# Battery_Board.net
KiCad netlist of a schematic drawn in EAGLE
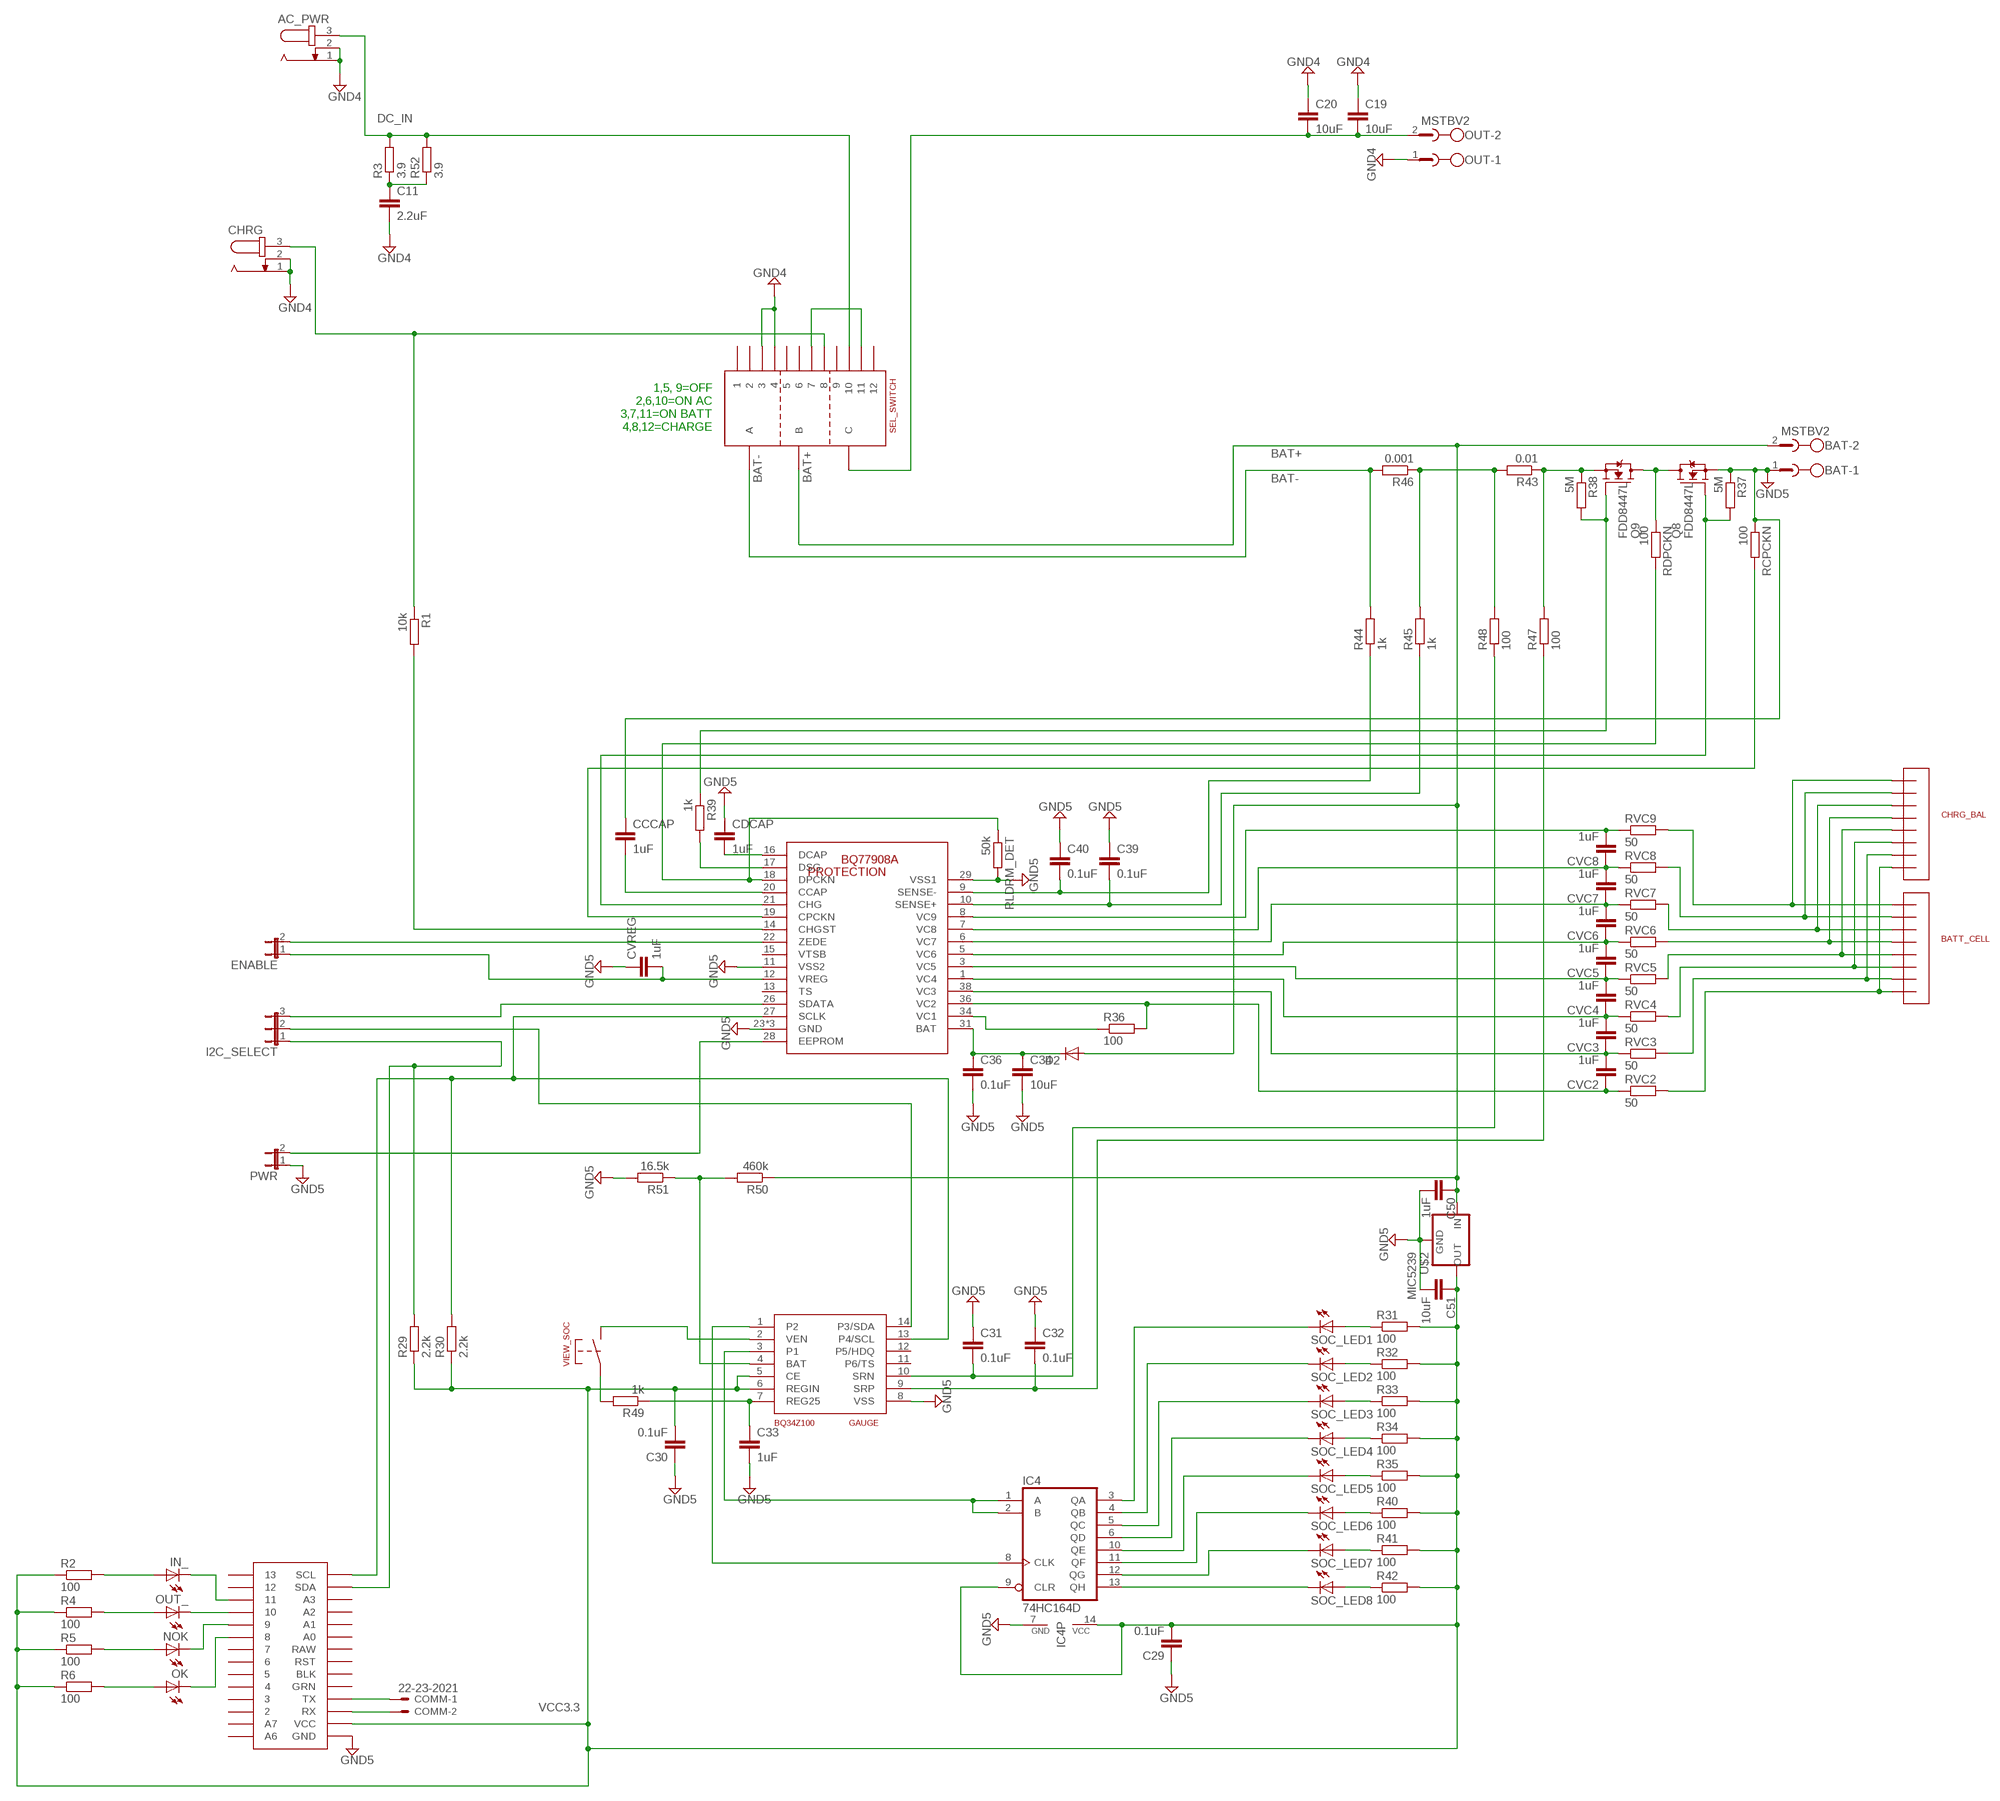
[diagram p0: schematic, sheet 1]

(export (version "E")
  (design (tool "Eeschema 10.0.6"))
  (components
    (comp (ref "AC_PWR")
      (value "JACK-PLUG1")
      (footprint "eagle-import:SPC4078")
      (libsource (lib "eagle-import") (part "JACK-PLUG1"))
    )
    (comp (ref "BAT")
      (value "MSTBV2")
      (footprint "eagle-import:MSTBV2")
      (fields
        (field (name "MPN") "MSTBV 2,5/2-GF-5.08")
        (field (name "MPN_1") "MSTBV 2,5/2-GF-5.08")
        (field (name "OC_FARNELL") "1792792")
        (field (name "OC_NEWARK") "69R9845")
      )
      (libsource (lib "eagle-import") (part "MSTBV2"))
    )
    (comp (ref "BATT_CELL")
      (value "JST-XH-8")
      (footprint "eagle-import:8PIN-2.5MM")
      (libsource (lib "eagle-import") (part "JST-XH-8"))
    )
    (comp (ref "C11")
      (value "2.2uF")
      (footprint "eagle-import:C1206")
      (libsource (lib "eagle-import") (part "C-EUC1206"))
    )
    (comp (ref "C19")
      (value "10uF")
      (footprint "eagle-import:C1812")
      (libsource (lib "eagle-import") (part "C-EUC1812"))
    )
    (comp (ref "C20")
      (value "10uF")
      (footprint "eagle-import:C1812")
      (libsource (lib "eagle-import") (part "C-EUC1812"))
    )
    (comp (ref "C29")
      (value "0.1uF")
      (footprint "eagle-import:C0603")
      (libsource (lib "eagle-import") (part "C-EUC0603"))
    )
    (comp (ref "C30")
      (value "0.1uF")
      (footprint "eagle-import:C0603")
      (libsource (lib "eagle-import") (part "C-EUC0603"))
    )
    (comp (ref "C31")
      (value "0.1uF")
      (footprint "eagle-import:C0603")
      (libsource (lib "eagle-import") (part "C-EUC0603"))
    )
    (comp (ref "C32")
      (value "0.1uF")
      (footprint "eagle-import:C0603")
      (libsource (lib "eagle-import") (part "C-EUC0603"))
    )
    (comp (ref "C33")
      (value "1uF")
      (footprint "eagle-import:C0603")
      (libsource (lib "eagle-import") (part "C-EUC0603"))
    )
    (comp (ref "C34")
      (value "10uF")
      (footprint "eagle-import:C1210")
      (libsource (lib "eagle-import") (part "C-EUC1210"))
    )
    (comp (ref "C36")
      (value "0.1uF")
      (footprint "eagle-import:C1210")
      (libsource (lib "eagle-import") (part "C-EUC1210"))
    )
    (comp (ref "C39")
      (value "0.1uF")
      (footprint "eagle-import:C0603")
      (libsource (lib "eagle-import") (part "C-EUC0603"))
    )
    (comp (ref "C40")
      (value "0.1uF")
      (footprint "eagle-import:C0603")
      (libsource (lib "eagle-import") (part "C-EUC0603"))
    )
    (comp (ref "C50")
      (value "1uF")
      (footprint "eagle-import:C0603")
      (libsource (lib "eagle-import") (part "C-EUC0603"))
    )
    (comp (ref "C51")
      (value "10uF")
      (footprint "eagle-import:C0603")
      (libsource (lib "eagle-import") (part "C-EUC0603"))
    )
    (comp (ref "CCCAP")
      (value "1uF")
      (footprint "eagle-import:C1206")
      (libsource (lib "eagle-import") (part "C-EUC1206"))
    )
    (comp (ref "CDCAP")
      (value "1uF")
      (footprint "eagle-import:C1206")
      (libsource (lib "eagle-import") (part "C-EUC1206"))
    )
    (comp (ref "CHRG")
      (value "JACK-PLUG1")
      (footprint "eagle-import:SPC4078")
      (libsource (lib "eagle-import") (part "JACK-PLUG1"))
    )
    (comp (ref "CHRG_BAL")
      (value "JST-XH-8")
      (footprint "eagle-import:8PIN-2.5MM")
      (libsource (lib "eagle-import") (part "JST-XH-8"))
    )
    (comp (ref "COMM")
      (value "22-23-2021")
      (footprint "eagle-import:22-23-2021")
      (fields (field (name "MF") "MOLEX"))
      (libsource (lib "eagle-import") (part "22-23-2021"))
    )
    (comp (ref "CVC2")
      (value "1uF")
      (footprint "eagle-import:C0603")
      (libsource (lib "eagle-import") (part "C-EUC0603"))
    )
    (comp (ref "CVC3")
      (value "1uF")
      (footprint "eagle-import:C0603")
      (libsource (lib "eagle-import") (part "C-EUC0603"))
    )
    (comp (ref "CVC4")
      (value "1uF")
      (footprint "eagle-import:C0603")
      (libsource (lib "eagle-import") (part "C-EUC0603"))
    )
    (comp (ref "CVC5")
      (value "1uF")
      (footprint "eagle-import:C0603")
      (libsource (lib "eagle-import") (part "C-EUC0603"))
    )
    (comp (ref "CVC6")
      (value "1uF")
      (footprint "eagle-import:C0603")
      (libsource (lib "eagle-import") (part "C-EUC0603"))
    )
    (comp (ref "CVC7")
      (value "1uF")
      (footprint "eagle-import:C0603")
      (libsource (lib "eagle-import") (part "C-EUC0603"))
    )
    (comp (ref "CVC8")
      (value "1uF")
      (footprint "eagle-import:C0603")
      (libsource (lib "eagle-import") (part "C-EUC0603"))
    )
    (comp (ref "CVREG")
      (value "1uF")
      (footprint "eagle-import:C0603")
      (libsource (lib "eagle-import") (part "C-EUC0603"))
    )
    (comp (ref "D2")
      (value "DIODE-SOD123")
      (footprint "eagle-import:SOD123")
      (libsource (lib "eagle-import") (part "DIODE-SOD123"))
    )
    (comp (ref "ENABLE")
      (value "JP1E")
      (footprint "eagle-import:JP1")
      (libsource (lib "eagle-import") (part "JP1E"))
    )
    (comp (ref "GAUGE")
      (value "BQ34Z100")
      (footprint "eagle-import:TSSOP-14-0.65MM")
      (libsource (lib "eagle-import") (part "BQ34Z100"))
    )
    (comp (ref "I2C_SELECT")
      (value "JP2E")
      (footprint "eagle-import:JP2")
      (libsource (lib "eagle-import") (part "JP2E"))
    )
    (comp (ref "IC4")
      (value "74HC164D")
      (footprint "eagle-import:SO14")
      (libsource (lib "eagle-import") (part "74164DHC"))
    )
    (comp (ref "IN_")
      (value "LEDCHIP-LED0603")
      (footprint "eagle-import:CHIP-LED0603")
      (libsource (lib "eagle-import") (part "LEDCHIP-LED0603"))
    )
    (comp (ref "NOK")
      (value "LEDCHIP-LED0603")
      (footprint "eagle-import:CHIP-LED0603")
      (libsource (lib "eagle-import") (part "LEDCHIP-LED0603"))
    )
    (comp (ref "OK")
      (value "LEDCHIP-LED0603")
      (footprint "eagle-import:CHIP-LED0603")
      (libsource (lib "eagle-import") (part "LEDCHIP-LED0603"))
    )
    (comp (ref "OUT")
      (value "MSTBV2")
      (footprint "eagle-import:MSTBV2")
      (fields
        (field (name "MPN") "MSTBV 2,5/2-GF-5.08")
        (field (name "MPN_1") "MSTBV 2,5/2-GF-5.08")
        (field (name "OC_FARNELL") "1792792")
        (field (name "OC_NEWARK") "69R9845")
      )
      (libsource (lib "eagle-import") (part "MSTBV2"))
    )
    (comp (ref "OUT_")
      (value "LEDCHIP-LED0603")
      (footprint "eagle-import:CHIP-LED0603")
      (libsource (lib "eagle-import") (part "LEDCHIP-LED0603"))
    )
    (comp (ref "PROTECTION")
      (value "BQ77908A")
      (footprint "eagle-import:TSSOP-38-0.5MM")
      (libsource (lib "eagle-import") (part "BQ77908A"))
    )
    (comp (ref "PWR")
      (value "JP1E")
      (footprint "eagle-import:JP1")
      (libsource (lib "eagle-import") (part "JP1E"))
    )
    (comp (ref "Q8")
      (value "FDD8447L")
      (footprint "eagle-import:TO252")
      (libsource (lib "eagle-import") (part "FDD8447L"))
    )
    (comp (ref "Q9")
      (value "FDD8447L")
      (footprint "eagle-import:TO252")
      (libsource (lib "eagle-import") (part "FDD8447L"))
    )
    (comp (ref "R1")
      (value "10k")
      (footprint "eagle-import:R0603")
      (libsource (lib "eagle-import") (part "R-EU_R0603"))
    )
    (comp (ref "R2")
      (value "100")
      (footprint "eagle-import:R0603")
      (libsource (lib "eagle-import") (part "R-EU_R0603"))
    )
    (comp (ref "R3")
      (value "3.9")
      (footprint "eagle-import:R1206")
      (libsource (lib "eagle-import") (part "R-EU_R1206"))
    )
    (comp (ref "R4")
      (value "100")
      (footprint "eagle-import:R0603")
      (libsource (lib "eagle-import") (part "R-EU_R0603"))
    )
    (comp (ref "R5")
      (value "100")
      (footprint "eagle-import:R0603")
      (libsource (lib "eagle-import") (part "R-EU_R0603"))
    )
    (comp (ref "R6")
      (value "100")
      (footprint "eagle-import:R0603")
      (libsource (lib "eagle-import") (part "R-EU_R0603"))
    )
    (comp (ref "R29")
      (value "2.2k")
      (footprint "eagle-import:R0603")
      (libsource (lib "eagle-import") (part "R-EU_R0603"))
    )
    (comp (ref "R30")
      (value "2.2k")
      (footprint "eagle-import:R0603")
      (libsource (lib "eagle-import") (part "R-EU_R0603"))
    )
    (comp (ref "R31")
      (value "100")
      (footprint "eagle-import:R0603")
      (libsource (lib "eagle-import") (part "R-EU_R0603"))
    )
    (comp (ref "R32")
      (value "100")
      (footprint "eagle-import:R0603")
      (libsource (lib "eagle-import") (part "R-EU_R0603"))
    )
    (comp (ref "R33")
      (value "100")
      (footprint "eagle-import:R0603")
      (libsource (lib "eagle-import") (part "R-EU_R0603"))
    )
    (comp (ref "R34")
      (value "100")
      (footprint "eagle-import:R0603")
      (libsource (lib "eagle-import") (part "R-EU_R0603"))
    )
    (comp (ref "R35")
      (value "100")
      (footprint "eagle-import:R0603")
      (libsource (lib "eagle-import") (part "R-EU_R0603"))
    )
    (comp (ref "R36")
      (value "100")
      (footprint "eagle-import:R0603")
      (libsource (lib "eagle-import") (part "R-EU_R0603"))
    )
    (comp (ref "R37")
      (value "5M")
      (footprint "eagle-import:R0603")
      (libsource (lib "eagle-import") (part "R-EU_R0603"))
    )
    (comp (ref "R38")
      (value "5M")
      (footprint "eagle-import:R0603")
      (libsource (lib "eagle-import") (part "R-EU_R0603"))
    )
    (comp (ref "R39")
      (value "1k")
      (footprint "eagle-import:R0603")
      (libsource (lib "eagle-import") (part "R-EU_R0603"))
    )
    (comp (ref "R40")
      (value "100")
      (footprint "eagle-import:R0603")
      (libsource (lib "eagle-import") (part "R-EU_R0603"))
    )
    (comp (ref "R41")
      (value "100")
      (footprint "eagle-import:R0603")
      (libsource (lib "eagle-import") (part "R-EU_R0603"))
    )
    (comp (ref "R42")
      (value "100")
      (footprint "eagle-import:R0603")
      (libsource (lib "eagle-import") (part "R-EU_R0603"))
    )
    (comp (ref "R43")
      (value "0.01")
      (footprint "eagle-import:R2010")
      (libsource (lib "eagle-import") (part "R-EU_R2010"))
    )
    (comp (ref "R44")
      (value "1k")
      (footprint "eagle-import:R0603")
      (libsource (lib "eagle-import") (part "R-EU_R0603"))
    )
    (comp (ref "R45")
      (value "1k")
      (footprint "eagle-import:R0603")
      (libsource (lib "eagle-import") (part "R-EU_R0603"))
    )
    (comp (ref "R46")
      (value "0.001")
      (footprint "eagle-import:R2010")
      (libsource (lib "eagle-import") (part "R-EU_R2010"))
    )
    (comp (ref "R47")
      (value "100")
      (footprint "eagle-import:R0603")
      (libsource (lib "eagle-import") (part "R-EU_R0603"))
    )
    (comp (ref "R48")
      (value "100")
      (footprint "eagle-import:R0603")
      (libsource (lib "eagle-import") (part "R-EU_R0603"))
    )
    (comp (ref "R49")
      (value "1k")
      (footprint "eagle-import:R0603")
      (libsource (lib "eagle-import") (part "R-EU_R0603"))
    )
    (comp (ref "R50")
      (value "460k")
      (footprint "eagle-import:R0805")
      (libsource (lib "eagle-import") (part "R-EU_R0805"))
    )
    (comp (ref "R51")
      (value "16.5k")
      (footprint "eagle-import:R0603")
      (libsource (lib "eagle-import") (part "R-EU_R0603"))
    )
    (comp (ref "R52")
      (value "3.9")
      (footprint "eagle-import:R1206")
      (libsource (lib "eagle-import") (part "R-EU_R1206"))
    )
    (comp (ref "RCPCKN")
      (value "100")
      (footprint "eagle-import:R0603")
      (libsource (lib "eagle-import") (part "R-EU_R0603"))
    )
    (comp (ref "RDPCKN")
      (value "100")
      (footprint "eagle-import:R0603")
      (libsource (lib "eagle-import") (part "R-EU_R0603"))
    )
    (comp (ref "RLDRM_DET")
      (value "50k")
      (footprint "eagle-import:R0603")
      (libsource (lib "eagle-import") (part "R-EU_R0603"))
    )
    (comp (ref "RVC2")
      (value "50")
      (footprint "eagle-import:R1206")
      (libsource (lib "eagle-import") (part "R-EU_R1206"))
    )
    (comp (ref "RVC3")
      (value "50")
      (footprint "eagle-import:R1206")
      (libsource (lib "eagle-import") (part "R-EU_R1206"))
    )
    (comp (ref "RVC4")
      (value "50")
      (footprint "eagle-import:R1206")
      (libsource (lib "eagle-import") (part "R-EU_R1206"))
    )
    (comp (ref "RVC5")
      (value "50")
      (footprint "eagle-import:R1206")
      (libsource (lib "eagle-import") (part "R-EU_R1206"))
    )
    (comp (ref "RVC6")
      (value "50")
      (footprint "eagle-import:R1206")
      (libsource (lib "eagle-import") (part "R-EU_R1206"))
    )
    (comp (ref "RVC7")
      (value "50")
      (footprint "eagle-import:R1206")
      (libsource (lib "eagle-import") (part "R-EU_R1206"))
    )
    (comp (ref "RVC8")
      (value "50")
      (footprint "eagle-import:R1206")
      (libsource (lib "eagle-import") (part "R-EU_R1206"))
    )
    (comp (ref "RVC9")
      (value "50")
      (footprint "eagle-import:R1206")
      (libsource (lib "eagle-import") (part "R-EU_R1206"))
    )
    (comp (ref "SEL_SWITCH")
      (value "CK1026")
      (footprint "eagle-import:CK1026")
      (libsource (lib "eagle-import") (part "CK1026"))
    )
    (comp (ref "SOC_LED1")
      (value "LEDCHIP-LED0603")
      (footprint "eagle-import:CHIP-LED0603")
      (libsource (lib "eagle-import") (part "LEDCHIP-LED0603"))
    )
    (comp (ref "SOC_LED2")
      (value "LEDCHIP-LED0603")
      (footprint "eagle-import:CHIP-LED0603")
      (libsource (lib "eagle-import") (part "LEDCHIP-LED0603"))
    )
    (comp (ref "SOC_LED3")
      (value "LEDCHIP-LED0603")
      (footprint "eagle-import:CHIP-LED0603")
      (libsource (lib "eagle-import") (part "LEDCHIP-LED0603"))
    )
    (comp (ref "SOC_LED4")
      (value "LEDCHIP-LED0603")
      (footprint "eagle-import:CHIP-LED0603")
      (libsource (lib "eagle-import") (part "LEDCHIP-LED0603"))
    )
    (comp (ref "SOC_LED5")
      (value "LEDCHIP-LED0603")
      (footprint "eagle-import:CHIP-LED0603")
      (libsource (lib "eagle-import") (part "LEDCHIP-LED0603"))
    )
    (comp (ref "SOC_LED6")
      (value "LEDCHIP-LED0603")
      (footprint "eagle-import:CHIP-LED0603")
      (libsource (lib "eagle-import") (part "LEDCHIP-LED0603"))
    )
    (comp (ref "SOC_LED7")
      (value "LEDCHIP-LED0603")
      (footprint "eagle-import:CHIP-LED0603")
      (libsource (lib "eagle-import") (part "LEDCHIP-LED0603"))
    )
    (comp (ref "SOC_LED8")
      (value "LEDCHIP-LED0603")
      (footprint "eagle-import:CHIP-LED0603")
      (libsource (lib "eagle-import") (part "LEDCHIP-LED0603"))
    )
    (comp (ref "U$1")
      (value "ARDUINO-MINI-PRO")
      (footprint "eagle-import:ARDUINO-MINI-PRO")
      (libsource (lib "eagle-import") (part "ARDUINO-MINI-PRO"))
    )
    (comp (ref "U$2")
      (value "MIC5239")
      (footprint "eagle-import:SOT223")
      (libsource (lib "eagle-import") (part "MIC5239"))
    )
    (comp (ref "VIEW_SOC")
      (value "PUSHBUTTON")
      (footprint "eagle-import:PUSHBUTTON")
      (libsource (lib "eagle-import") (part "PUSHBUTTON"))
    )
  )
  (nets
    (net (code "1") (name "/BAT+") (class "Default")
      (node (ref "BAT") (pin "2") (pinfunction "1_2") (pintype "passive"))
      (node (ref "C50") (pin "1") (pinfunction "1_1") (pintype "passive"))
      (node (ref "D2") (pin "A") (pinfunction "A_A") (pintype "passive"))
      (node (ref "R50") (pin "1") (pinfunction "1_1") (pintype "passive"))
      (node (ref "SEL_SWITCH") (pin "B") (pinfunction "B_B") (pintype "bidirectional"))
      (node (ref "U$2") (pin "1") (pinfunction "IN_1") (pintype "input"))
    )
    (net (code "2") (name "/BAT-") (class "Default")
      (node (ref "R44") (pin "2") (pinfunction "2_2") (pintype "passive"))
      (node (ref "R46") (pin "2") (pinfunction "2_2") (pintype "passive"))
      (node (ref "SEL_SWITCH") (pin "A") (pinfunction "A_A") (pintype "bidirectional"))
    )
    (net (code "3") (name "/DC_IN") (class "Default")
      (node (ref "AC_PWR") (pin "3") (pinfunction "3_3") (pintype "passive"))
      (node (ref "R3") (pin "2") (pinfunction "2_2") (pintype "passive"))
      (node (ref "R52") (pin "2") (pinfunction "2_2") (pintype "passive"))
      (node (ref "SEL_SWITCH") (pin "10") (pinfunction "10_10") (pintype "bidirectional"))
    )
    (net (code "4") (name "/VCC3.3") (class "Default")
      (node (ref "C29") (pin "2") (pinfunction "2_2") (pintype "passive"))
      (node (ref "C30") (pin "2") (pinfunction "2_2") (pintype "passive"))
      (node (ref "C51") (pin "1") (pinfunction "1_1") (pintype "passive"))
      (node (ref "GAUGE") (pin "5") (pinfunction "CE_5") (pintype "bidirectional"))
      (node (ref "GAUGE") (pin "6") (pinfunction "REGIN_6") (pintype "bidirectional"))
      (node (ref "IC4") (pin "14") (pinfunction "VCC_14") (pintype "power_in"))
      (node (ref "IC4") (pin "9") (pinfunction "CLR_9") (pintype "input"))
      (node (ref "R2") (pin "1") (pinfunction "1_1") (pintype "passive"))
      (node (ref "R29") (pin "1") (pinfunction "1_1") (pintype "passive"))
      (node (ref "R30") (pin "1") (pinfunction "1_1") (pintype "passive"))
      (node (ref "R31") (pin "2") (pinfunction "2_2") (pintype "passive"))
      (node (ref "R32") (pin "2") (pinfunction "2_2") (pintype "passive"))
      (node (ref "R33") (pin "2") (pinfunction "2_2") (pintype "passive"))
      (node (ref "R34") (pin "2") (pinfunction "2_2") (pintype "passive"))
      (node (ref "R35") (pin "2") (pinfunction "2_2") (pintype "passive"))
      (node (ref "R4") (pin "1") (pinfunction "1_1") (pintype "passive"))
      (node (ref "R40") (pin "2") (pinfunction "2_2") (pintype "passive"))
      (node (ref "R41") (pin "2") (pinfunction "2_2") (pintype "passive"))
      (node (ref "R42") (pin "2") (pinfunction "2_2") (pintype "passive"))
      (node (ref "R5") (pin "1") (pinfunction "1_1") (pintype "passive"))
      (node (ref "R6") (pin "1") (pinfunction "1_1") (pintype "passive"))
      (node (ref "U$1") (pin "VCC") (pinfunction "VCC_VCC") (pintype "bidirectional"))
      (node (ref "U$2") (pin "3") (pinfunction "OUT_3") (pintype "passive"))
    )
    (net (code "5") (name "GND4") (class "Default")
      (node (ref "AC_PWR") (pin "1") (pinfunction "1_1") (pintype "passive"))
      (node (ref "AC_PWR") (pin "2") (pinfunction "2_2") (pintype "passive"))
      (node (ref "C11") (pin "2") (pinfunction "2_2") (pintype "passive"))
      (node (ref "C19") (pin "1") (pinfunction "1_1") (pintype "passive"))
      (node (ref "C20") (pin "1") (pinfunction "1_1") (pintype "passive"))
      (node (ref "CHRG") (pin "1") (pinfunction "1_1") (pintype "passive"))
      (node (ref "CHRG") (pin "2") (pinfunction "2_2") (pintype "passive"))
      (node (ref "OUT") (pin "1") (pinfunction "1_1") (pintype "passive"))
      (node (ref "SEL_SWITCH") (pin "3") (pinfunction "3_3") (pintype "bidirectional"))
      (node (ref "SEL_SWITCH") (pin "4") (pinfunction "4_4") (pintype "bidirectional"))
    )
    (net (code "6") (name "GND5") (class "Default")
      (node (ref "BAT") (pin "1") (pinfunction "1_1") (pintype "passive"))
      (node (ref "C29") (pin "1") (pinfunction "1_1") (pintype "passive"))
      (node (ref "C30") (pin "1") (pinfunction "1_1") (pintype "passive"))
      (node (ref "C31") (pin "1") (pinfunction "1_1") (pintype "passive"))
      (node (ref "C32") (pin "1") (pinfunction "1_1") (pintype "passive"))
      (node (ref "C33") (pin "2") (pinfunction "2_2") (pintype "passive"))
      (node (ref "C34") (pin "2") (pinfunction "2_2") (pintype "passive"))
      (node (ref "C36") (pin "2") (pinfunction "2_2") (pintype "passive"))
      (node (ref "C39") (pin "1") (pinfunction "1_1") (pintype "passive"))
      (node (ref "C40") (pin "1") (pinfunction "1_1") (pintype "passive"))
      (node (ref "C50") (pin "2") (pinfunction "2_2") (pintype "passive"))
      (node (ref "C51") (pin "2") (pinfunction "2_2") (pintype "passive"))
      (node (ref "CCCAP") (pin "1") (pinfunction "1_1") (pintype "passive"))
      (node (ref "CDCAP") (pin "1") (pinfunction "1_1") (pintype "passive"))
      (node (ref "CVREG") (pin "1") (pinfunction "1_1") (pintype "passive"))
      (node (ref "GAUGE") (pin "8") (pinfunction "VSS_8") (pintype "bidirectional"))
      (node (ref "IC4") (pin "7") (pinfunction "GND_7") (pintype "power_in"))
      (node (ref "PROTECTION") (pin "11") (pinfunction "VSS2_11") (pintype "bidirectional"))
      (node (ref "PROTECTION") (pin "23") (pinfunction "GND_23") (pintype "bidirectional"))
      (node (ref "PROTECTION") (pin "24") (pinfunction "GND_24") (pintype "bidirectional"))
      (node (ref "PROTECTION") (pin "25") (pinfunction "GND_25") (pintype "bidirectional"))
      (node (ref "PROTECTION") (pin "29") (pinfunction "VSS1_29") (pintype "bidirectional"))
      (node (ref "PWR") (pin "1") (pinfunction "1_1") (pintype "passive"))
      (node (ref "Q8") (pin "2") (pinfunction "S_2") (pintype "passive"))
      (node (ref "R37") (pin "1") (pinfunction "1_1") (pintype "passive"))
      (node (ref "R51") (pin "2") (pinfunction "2_2") (pintype "passive"))
      (node (ref "RCPCKN") (pin "1") (pinfunction "1_1") (pintype "passive"))
      (node (ref "RLDRM_DET") (pin "2") (pinfunction "2_2") (pintype "passive"))
      (node (ref "U$1") (pin "GND") (pinfunction "GND_GND") (pintype "bidirectional"))
      (node (ref "U$2") (pin "2") (pinfunction "GND_2") (pintype "input"))
      (node (ref "U$2") (pin "4") (pinfunction "GND_4") (pintype "input"))
    )
    (net (code "7") (name "Net-(BATT_CELL-PadP$1)") (class "Default")
      (node (ref "BATT_CELL") (pin "P$1") (pinfunction "P$1_P$1") (pintype "bidirectional"))
      (node (ref "CHRG_BAL") (pin "P$1") (pinfunction "P$1_P$1") (pintype "bidirectional"))
      (node (ref "RVC9") (pin "2") (pinfunction "2_2") (pintype "passive"))
    )
    (net (code "8") (name "Net-(BATT_CELL-PadP$2)") (class "Default")
      (node (ref "BATT_CELL") (pin "P$2") (pinfunction "P$2_P$2") (pintype "bidirectional"))
      (node (ref "CHRG_BAL") (pin "P$2") (pinfunction "P$2_P$2") (pintype "bidirectional"))
      (node (ref "RVC8") (pin "2") (pinfunction "2_2") (pintype "passive"))
    )
    (net (code "9") (name "Net-(BATT_CELL-PadP$3)") (class "Default")
      (node (ref "BATT_CELL") (pin "P$3") (pinfunction "P$3_P$3") (pintype "bidirectional"))
      (node (ref "CHRG_BAL") (pin "P$3") (pinfunction "P$3_P$3") (pintype "bidirectional"))
      (node (ref "RVC7") (pin "2") (pinfunction "2_2") (pintype "passive"))
    )
    (net (code "10") (name "Net-(BATT_CELL-PadP$4)") (class "Default")
      (node (ref "BATT_CELL") (pin "P$4") (pinfunction "P$4_P$4") (pintype "bidirectional"))
      (node (ref "CHRG_BAL") (pin "P$4") (pinfunction "P$4_P$4") (pintype "bidirectional"))
      (node (ref "RVC6") (pin "2") (pinfunction "2_2") (pintype "passive"))
    )
    (net (code "11") (name "Net-(BATT_CELL-PadP$5)") (class "Default")
      (node (ref "BATT_CELL") (pin "P$5") (pinfunction "P$5_P$5") (pintype "bidirectional"))
      (node (ref "CHRG_BAL") (pin "P$5") (pinfunction "P$5_P$5") (pintype "bidirectional"))
      (node (ref "RVC5") (pin "2") (pinfunction "2_2") (pintype "passive"))
    )
    (net (code "12") (name "Net-(BATT_CELL-PadP$6)") (class "Default")
      (node (ref "BATT_CELL") (pin "P$6") (pinfunction "P$6_P$6") (pintype "bidirectional"))
      (node (ref "CHRG_BAL") (pin "P$6") (pinfunction "P$6_P$6") (pintype "bidirectional"))
      (node (ref "RVC4") (pin "2") (pinfunction "2_2") (pintype "passive"))
    )
    (net (code "13") (name "Net-(BATT_CELL-PadP$7)") (class "Default")
      (node (ref "BATT_CELL") (pin "P$7") (pinfunction "P$7_P$7") (pintype "bidirectional"))
      (node (ref "CHRG_BAL") (pin "P$7") (pinfunction "P$7_P$7") (pintype "bidirectional"))
      (node (ref "RVC3") (pin "2") (pinfunction "2_2") (pintype "passive"))
    )
    (net (code "14") (name "Net-(BATT_CELL-PadP$8)") (class "Default")
      (node (ref "BATT_CELL") (pin "P$8") (pinfunction "P$8_P$8") (pintype "bidirectional"))
      (node (ref "CHRG_BAL") (pin "P$8") (pinfunction "P$8_P$8") (pintype "bidirectional"))
      (node (ref "RVC2") (pin "2") (pinfunction "2_2") (pintype "passive"))
    )
    (net (code "15") (name "Net-(C11-Pad1)") (class "Default")
      (node (ref "C11") (pin "1") (pinfunction "1_1") (pintype "passive"))
      (node (ref "R3") (pin "1") (pinfunction "1_1") (pintype "passive"))
      (node (ref "R52") (pin "1") (pinfunction "1_1") (pintype "passive"))
    )
    (net (code "16") (name "Net-(CHRG-Pad3)") (class "Default")
      (node (ref "CHRG") (pin "3") (pinfunction "3_3") (pintype "passive"))
      (node (ref "R1") (pin "1") (pinfunction "1_1") (pintype "passive"))
      (node (ref "SEL_SWITCH") (pin "8") (pinfunction "8_8") (pintype "bidirectional"))
    )
    (net (code "17") (name "Net-(COMMA-S)") (class "Default")
      (node (ref "COMM") (pin "1") (pinfunction "S_1") (pintype "passive"))
      (node (ref "U$1") (pin "TXO") (pinfunction "TX_TXO") (pintype "bidirectional"))
    )
    (net (code "18") (name "Net-(COMMB-S)") (class "Default")
      (node (ref "COMM") (pin "2") (pinfunction "S_2") (pintype "passive"))
      (node (ref "U$1") (pin "RXI") (pinfunction "RX_RXI") (pintype "bidirectional"))
    )
    (net (code "19") (name "Net-(GAUGE-BAT)") (class "Default")
      (node (ref "GAUGE") (pin "4") (pinfunction "BAT_4") (pintype "bidirectional"))
      (node (ref "R50") (pin "2") (pinfunction "2_2") (pintype "passive"))
      (node (ref "R51") (pin "1") (pinfunction "1_1") (pintype "passive"))
    )
    (net (code "20") (name "Net-(GAUGE-P1)") (class "Default")
      (node (ref "GAUGE") (pin "3") (pinfunction "P1_3") (pintype "bidirectional"))
      (node (ref "IC4") (pin "1") (pinfunction "A_1") (pintype "input"))
      (node (ref "IC4") (pin "2") (pinfunction "B_2") (pintype "input"))
    )
    (net (code "21") (name "Net-(GAUGE-P2)") (class "Default")
      (node (ref "GAUGE") (pin "1") (pinfunction "P2_1") (pintype "bidirectional"))
      (node (ref "IC4") (pin "8") (pinfunction "CLK_8") (pintype "input"))
    )
    (net (code "22") (name "Net-(GAUGE-P3{slash}SDA)") (class "Default")
      (node (ref "GAUGE") (pin "14") (pinfunction "P3/SDA_14") (pintype "bidirectional"))
      (node (ref "I2C_SELECT") (pin "2") (pinfunction "2_2") (pintype "passive"))
    )
    (net (code "23") (name "Net-(GAUGE-P4{slash}SCL)") (class "Default")
      (node (ref "GAUGE") (pin "13") (pinfunction "P4/SCL_13") (pintype "bidirectional"))
      (node (ref "PROTECTION") (pin "27") (pinfunction "SCLK_27") (pintype "bidirectional"))
      (node (ref "R30") (pin "2") (pinfunction "2_2") (pintype "passive"))
      (node (ref "U$1") (pin "A5") (pinfunction "SCL_A5") (pintype "bidirectional"))
    )
    (net (code "24") (name "Net-(GAUGE-REG25)") (class "Default")
      (node (ref "C33") (pin "1") (pinfunction "1_1") (pintype "passive"))
      (node (ref "GAUGE") (pin "7") (pinfunction "REG25_7") (pintype "bidirectional"))
      (node (ref "R49") (pin "1") (pinfunction "1_1") (pintype "passive"))
    )
    (net (code "25") (name "Net-(GAUGE-SRN)") (class "Default")
      (node (ref "C31") (pin "2") (pinfunction "2_2") (pintype "passive"))
      (node (ref "GAUGE") (pin "10") (pinfunction "SRN_10") (pintype "bidirectional"))
      (node (ref "R48") (pin "1") (pinfunction "1_1") (pintype "passive"))
    )
    (net (code "26") (name "Net-(GAUGE-SRP)") (class "Default")
      (node (ref "C32") (pin "2") (pinfunction "2_2") (pintype "passive"))
      (node (ref "GAUGE") (pin "9") (pinfunction "SRP_9") (pintype "bidirectional"))
      (node (ref "R47") (pin "1") (pinfunction "1_1") (pintype "passive"))
    )
    (net (code "27") (name "Net-(GAUGE-VEN)") (class "Default")
      (node (ref "GAUGE") (pin "2") (pinfunction "VEN_2") (pintype "bidirectional"))
      (node (ref "VIEW_SOC") (pin "P$3") (pinfunction "P$2_P$3") (pintype "bidirectional"))
      (node (ref "VIEW_SOC") (pin "P$4") (pinfunction "P$2_P$4") (pintype "bidirectional"))
    )
    (net (code "28") (name "Net-(IC4A-QA)") (class "Default")
      (node (ref "IC4") (pin "3") (pinfunction "QA_3") (pintype "output"))
      (node (ref "SOC_LED1") (pin "C") (pinfunction "C_C") (pintype "passive"))
    )
    (net (code "29") (name "Net-(IC4A-QB)") (class "Default")
      (node (ref "IC4") (pin "4") (pinfunction "QB_4") (pintype "output"))
      (node (ref "SOC_LED2") (pin "C") (pinfunction "C_C") (pintype "passive"))
    )
    (net (code "30") (name "Net-(IC4A-QC)") (class "Default")
      (node (ref "IC4") (pin "5") (pinfunction "QC_5") (pintype "output"))
      (node (ref "SOC_LED3") (pin "C") (pinfunction "C_C") (pintype "passive"))
    )
    (net (code "31") (name "Net-(IC4A-QD)") (class "Default")
      (node (ref "IC4") (pin "6") (pinfunction "QD_6") (pintype "output"))
      (node (ref "SOC_LED4") (pin "C") (pinfunction "C_C") (pintype "passive"))
    )
    (net (code "32") (name "Net-(IC4A-QE)") (class "Default")
      (node (ref "IC4") (pin "10") (pinfunction "QE_10") (pintype "output"))
      (node (ref "SOC_LED5") (pin "C") (pinfunction "C_C") (pintype "passive"))
    )
    (net (code "33") (name "Net-(IC4A-QF)") (class "Default")
      (node (ref "IC4") (pin "11") (pinfunction "QF_11") (pintype "output"))
      (node (ref "SOC_LED6") (pin "C") (pinfunction "C_C") (pintype "passive"))
    )
    (net (code "34") (name "Net-(IC4A-QG)") (class "Default")
      (node (ref "IC4") (pin "12") (pinfunction "QG_12") (pintype "output"))
      (node (ref "SOC_LED7") (pin "C") (pinfunction "C_C") (pintype "passive"))
    )
    (net (code "35") (name "Net-(IC4A-QH)") (class "Default")
      (node (ref "IC4") (pin "13") (pinfunction "QH_13") (pintype "output"))
      (node (ref "SOC_LED8") (pin "C") (pinfunction "C_C") (pintype "passive"))
    )
    (net (code "36") (name "Net-(IN_-PadA)") (class "Default")
      (node (ref "IN_") (pin "A") (pinfunction "A_A") (pintype "passive"))
      (node (ref "R2") (pin "2") (pinfunction "2_2") (pintype "passive"))
    )
    (net (code "37") (name "Net-(IN_-PadC)") (class "Default")
      (node (ref "IN_") (pin "C") (pinfunction "C_C") (pintype "passive"))
      (node (ref "U$1") (pin "11") (pinfunction "11_11") (pintype "bidirectional"))
    )
    (net (code "38") (name "Net-(NOK-PadA)") (class "Default")
      (node (ref "NOK") (pin "A") (pinfunction "A_A") (pintype "passive"))
      (node (ref "R5") (pin "2") (pinfunction "2_2") (pintype "passive"))
    )
    (net (code "39") (name "Net-(NOK-PadC)") (class "Default")
      (node (ref "NOK") (pin "C") (pinfunction "C_C") (pintype "passive"))
      (node (ref "U$1") (pin "9") (pinfunction "9_9") (pintype "bidirectional"))
    )
    (net (code "40") (name "Net-(OK-PadA)") (class "Default")
      (node (ref "OK") (pin "A") (pinfunction "A_A") (pintype "passive"))
      (node (ref "R6") (pin "2") (pinfunction "2_2") (pintype "passive"))
    )
    (net (code "41") (name "Net-(OK-PadC)") (class "Default")
      (node (ref "OK") (pin "C") (pinfunction "C_C") (pintype "passive"))
      (node (ref "U$1") (pin "8") (pinfunction "8_8") (pintype "bidirectional"))
    )
    (net (code "42") (name "Net-(OUTB-1)") (class "Default")
      (node (ref "C19") (pin "2") (pinfunction "2_2") (pintype "passive"))
      (node (ref "C20") (pin "2") (pinfunction "2_2") (pintype "passive"))
      (node (ref "OUT") (pin "2") (pinfunction "1_2") (pintype "passive"))
      (node (ref "SEL_SWITCH") (pin "C") (pinfunction "C_C") (pintype "bidirectional"))
    )
    (net (code "43") (name "Net-(OUT_-PadA)") (class "Default")
      (node (ref "OUT_") (pin "A") (pinfunction "A_A") (pintype "passive"))
      (node (ref "R4") (pin "2") (pinfunction "2_2") (pintype "passive"))
    )
    (net (code "44") (name "Net-(OUT_-PadC)") (class "Default")
      (node (ref "OUT_") (pin "C") (pinfunction "C_C") (pintype "passive"))
      (node (ref "U$1") (pin "10") (pinfunction "10_10") (pintype "bidirectional"))
    )
    (net (code "45") (name "Net-(PROTECTION-BAT)") (class "Default")
      (node (ref "C34") (pin "1") (pinfunction "1_1") (pintype "passive"))
      (node (ref "C36") (pin "1") (pinfunction "1_1") (pintype "passive"))
      (node (ref "D2") (pin "C") (pinfunction "C_C") (pintype "passive"))
      (node (ref "PROTECTION") (pin "31") (pinfunction "BAT_31") (pintype "bidirectional"))
    )
    (net (code "46") (name "Net-(PROTECTION-CCAP)") (class "Default")
      (node (ref "CCCAP") (pin "2") (pinfunction "2_2") (pintype "passive"))
      (node (ref "PROTECTION") (pin "20") (pinfunction "CCAP_20") (pintype "bidirectional"))
    )
    (net (code "47") (name "Net-(PROTECTION-CHG)") (class "Default")
      (node (ref "PROTECTION") (pin "21") (pinfunction "CHG_21") (pintype "bidirectional"))
      (node (ref "Q8") (pin "1") (pinfunction "G_1") (pintype "passive"))
      (node (ref "R37") (pin "2") (pinfunction "2_2") (pintype "passive"))
    )
    (net (code "48") (name "Net-(PROTECTION-CHGST)") (class "Default")
      (node (ref "PROTECTION") (pin "14") (pinfunction "CHGST_14") (pintype "bidirectional"))
      (node (ref "R1") (pin "2") (pinfunction "2_2") (pintype "passive"))
    )
    (net (code "49") (name "Net-(PROTECTION-CPCKN)") (class "Default")
      (node (ref "PROTECTION") (pin "19") (pinfunction "CPCKN_19") (pintype "bidirectional"))
      (node (ref "RCPCKN") (pin "2") (pinfunction "2_2") (pintype "passive"))
    )
    (net (code "50") (name "Net-(PROTECTION-DCAP)") (class "Default")
      (node (ref "CDCAP") (pin "2") (pinfunction "2_2") (pintype "passive"))
      (node (ref "PROTECTION") (pin "16") (pinfunction "DCAP_16") (pintype "bidirectional"))
    )
    (net (code "51") (name "Net-(PROTECTION-DPCKN)") (class "Default")
      (node (ref "PROTECTION") (pin "18") (pinfunction "DPCKN_18") (pintype "bidirectional"))
      (node (ref "RDPCKN") (pin "2") (pinfunction "2_2") (pintype "passive"))
      (node (ref "RLDRM_DET") (pin "1") (pinfunction "1_1") (pintype "passive"))
    )
    (net (code "52") (name "Net-(PROTECTION-DSG)") (class "Default")
      (node (ref "PROTECTION") (pin "17") (pinfunction "DSG_17") (pintype "bidirectional"))
      (node (ref "R39") (pin "2") (pinfunction "2_2") (pintype "passive"))
    )
    (net (code "53") (name "Net-(PROTECTION-EEPROM)") (class "Default")
      (node (ref "PROTECTION") (pin "28") (pinfunction "EEPROM_28") (pintype "bidirectional"))
      (node (ref "PWR") (pin "2") (pinfunction "2_2") (pintype "passive"))
    )
    (net (code "54") (name "Net-(PROTECTION-SDATA)") (class "Default")
      (node (ref "I2C_SELECT") (pin "3") (pinfunction "3_3") (pintype "passive"))
      (node (ref "PROTECTION") (pin "26") (pinfunction "SDATA_26") (pintype "bidirectional"))
    )
    (net (code "55") (name "Net-(PROTECTION-SENSE+)") (class "Default")
      (node (ref "C39") (pin "2") (pinfunction "2_2") (pintype "passive"))
      (node (ref "PROTECTION") (pin "10") (pinfunction "SENSE+_10") (pintype "bidirectional"))
      (node (ref "R45") (pin "1") (pinfunction "1_1") (pintype "passive"))
    )
    (net (code "56") (name "Net-(PROTECTION-SENSE-)") (class "Default")
      (node (ref "C40") (pin "2") (pinfunction "2_2") (pintype "passive"))
      (node (ref "PROTECTION") (pin "9") (pinfunction "SENSE-_9") (pintype "bidirectional"))
      (node (ref "R44") (pin "1") (pinfunction "1_1") (pintype "passive"))
    )
    (net (code "57") (name "Net-(PROTECTION-VC1)") (class "Default")
      (node (ref "PROTECTION") (pin "34") (pinfunction "VC1_34") (pintype "bidirectional"))
      (node (ref "R36") (pin "1") (pinfunction "1_1") (pintype "passive"))
    )
    (net (code "58") (name "Net-(PROTECTION-VC2)") (class "Default")
      (node (ref "CVC2") (pin "1") (pinfunction "1_1") (pintype "passive"))
      (node (ref "PROTECTION") (pin "36") (pinfunction "VC2_36") (pintype "bidirectional"))
      (node (ref "R36") (pin "2") (pinfunction "2_2") (pintype "passive"))
      (node (ref "RVC2") (pin "1") (pinfunction "1_1") (pintype "passive"))
    )
    (net (code "59") (name "Net-(PROTECTION-VC3)") (class "Default")
      (node (ref "CVC2") (pin "2") (pinfunction "2_2") (pintype "passive"))
      (node (ref "CVC3") (pin "1") (pinfunction "1_1") (pintype "passive"))
      (node (ref "PROTECTION") (pin "38") (pinfunction "VC3_38") (pintype "bidirectional"))
      (node (ref "RVC3") (pin "1") (pinfunction "1_1") (pintype "passive"))
    )
    (net (code "60") (name "Net-(PROTECTION-VC4)") (class "Default")
      (node (ref "CVC3") (pin "2") (pinfunction "2_2") (pintype "passive"))
      (node (ref "CVC4") (pin "1") (pinfunction "1_1") (pintype "passive"))
      (node (ref "PROTECTION") (pin "1") (pinfunction "VC4_1") (pintype "bidirectional"))
      (node (ref "RVC4") (pin "1") (pinfunction "1_1") (pintype "passive"))
    )
    (net (code "61") (name "Net-(PROTECTION-VC5)") (class "Default")
      (node (ref "CVC4") (pin "2") (pinfunction "2_2") (pintype "passive"))
      (node (ref "CVC5") (pin "1") (pinfunction "1_1") (pintype "passive"))
      (node (ref "PROTECTION") (pin "3") (pinfunction "VC5_3") (pintype "bidirectional"))
      (node (ref "RVC5") (pin "1") (pinfunction "1_1") (pintype "passive"))
    )
    (net (code "62") (name "Net-(PROTECTION-VC6)") (class "Default")
      (node (ref "CVC5") (pin "2") (pinfunction "2_2") (pintype "passive"))
      (node (ref "CVC6") (pin "1") (pinfunction "1_1") (pintype "passive"))
      (node (ref "PROTECTION") (pin "5") (pinfunction "VC6_5") (pintype "bidirectional"))
      (node (ref "RVC6") (pin "1") (pinfunction "1_1") (pintype "passive"))
    )
    (net (code "63") (name "Net-(PROTECTION-VC7)") (class "Default")
      (node (ref "CVC6") (pin "2") (pinfunction "2_2") (pintype "passive"))
      (node (ref "CVC7") (pin "1") (pinfunction "1_1") (pintype "passive"))
      (node (ref "PROTECTION") (pin "6") (pinfunction "VC7_6") (pintype "bidirectional"))
      (node (ref "RVC7") (pin "1") (pinfunction "1_1") (pintype "passive"))
    )
    (net (code "64") (name "Net-(PROTECTION-VC8)") (class "Default")
      (node (ref "CVC7") (pin "2") (pinfunction "2_2") (pintype "passive"))
      (node (ref "CVC8") (pin "1") (pinfunction "1_1") (pintype "passive"))
      (node (ref "PROTECTION") (pin "7") (pinfunction "VC8_7") (pintype "bidirectional"))
      (node (ref "RVC8") (pin "1") (pinfunction "1_1") (pintype "passive"))
    )
    (net (code "65") (name "Net-(PROTECTION-VC9)") (class "Default")
      (node (ref "CVC8") (pin "2") (pinfunction "2_2") (pintype "passive"))
      (node (ref "PROTECTION") (pin "8") (pinfunction "VC9_8") (pintype "bidirectional"))
      (node (ref "RVC9") (pin "1") (pinfunction "1_1") (pintype "passive"))
    )
    (net (code "66") (name "Net-(PROTECTION-VREG)") (class "Default")
      (node (ref "CVREG") (pin "2") (pinfunction "2_2") (pintype "passive"))
      (node (ref "ENABLE") (pin "1") (pinfunction "1_1") (pintype "passive"))
      (node (ref "PROTECTION") (pin "12") (pinfunction "VREG_12") (pintype "bidirectional"))
    )
    (net (code "67") (name "Net-(PROTECTION-ZEDE)") (class "Default")
      (node (ref "ENABLE") (pin "2") (pinfunction "2_2") (pintype "passive"))
      (node (ref "PROTECTION") (pin "22") (pinfunction "ZEDE_22") (pintype "bidirectional"))
    )
    (net (code "68") (name "Net-(Q8-D)") (class "Default")
      (node (ref "Q8") (pin "3") (pinfunction "D_3") (pintype "passive"))
      (node (ref "Q9") (pin "3") (pinfunction "D_3") (pintype "passive"))
      (node (ref "RDPCKN") (pin "1") (pinfunction "1_1") (pintype "passive"))
    )
    (net (code "69") (name "Net-(Q9-G)") (class "Default")
      (node (ref "Q9") (pin "1") (pinfunction "G_1") (pintype "passive"))
      (node (ref "R38") (pin "2") (pinfunction "2_2") (pintype "passive"))
      (node (ref "R39") (pin "1") (pinfunction "1_1") (pintype "passive"))
    )
    (net (code "70") (name "Net-(Q9-S)") (class "Default")
      (node (ref "Q9") (pin "2") (pinfunction "S_2") (pintype "passive"))
      (node (ref "R38") (pin "1") (pinfunction "1_1") (pintype "passive"))
      (node (ref "R43") (pin "1") (pinfunction "1_1") (pintype "passive"))
      (node (ref "R47") (pin "2") (pinfunction "2_2") (pintype "passive"))
    )
    (net (code "71") (name "Net-(R31-Pad1)") (class "Default")
      (node (ref "R31") (pin "1") (pinfunction "1_1") (pintype "passive"))
      (node (ref "SOC_LED1") (pin "A") (pinfunction "A_A") (pintype "passive"))
    )
    (net (code "72") (name "Net-(R32-Pad1)") (class "Default")
      (node (ref "R32") (pin "1") (pinfunction "1_1") (pintype "passive"))
      (node (ref "SOC_LED2") (pin "A") (pinfunction "A_A") (pintype "passive"))
    )
    (net (code "73") (name "Net-(R33-Pad1)") (class "Default")
      (node (ref "R33") (pin "1") (pinfunction "1_1") (pintype "passive"))
      (node (ref "SOC_LED3") (pin "A") (pinfunction "A_A") (pintype "passive"))
    )
    (net (code "74") (name "Net-(R34-Pad1)") (class "Default")
      (node (ref "R34") (pin "1") (pinfunction "1_1") (pintype "passive"))
      (node (ref "SOC_LED4") (pin "A") (pinfunction "A_A") (pintype "passive"))
    )
    (net (code "75") (name "Net-(R35-Pad1)") (class "Default")
      (node (ref "R35") (pin "1") (pinfunction "1_1") (pintype "passive"))
      (node (ref "SOC_LED5") (pin "A") (pinfunction "A_A") (pintype "passive"))
    )
    (net (code "76") (name "Net-(R40-Pad1)") (class "Default")
      (node (ref "R40") (pin "1") (pinfunction "1_1") (pintype "passive"))
      (node (ref "SOC_LED6") (pin "A") (pinfunction "A_A") (pintype "passive"))
    )
    (net (code "77") (name "Net-(R41-Pad1)") (class "Default")
      (node (ref "R41") (pin "1") (pinfunction "1_1") (pintype "passive"))
      (node (ref "SOC_LED7") (pin "A") (pinfunction "A_A") (pintype "passive"))
    )
    (net (code "78") (name "Net-(R42-Pad1)") (class "Default")
      (node (ref "R42") (pin "1") (pinfunction "1_1") (pintype "passive"))
      (node (ref "SOC_LED8") (pin "A") (pinfunction "A_A") (pintype "passive"))
    )
    (net (code "79") (name "Net-(R43-Pad2)") (class "Default")
      (node (ref "R43") (pin "2") (pinfunction "2_2") (pintype "passive"))
      (node (ref "R45") (pin "2") (pinfunction "2_2") (pintype "passive"))
      (node (ref "R46") (pin "1") (pinfunction "1_1") (pintype "passive"))
      (node (ref "R48") (pin "2") (pinfunction "2_2") (pintype "passive"))
    )
    (net (code "80") (name "Net-(R49-Pad2)") (class "Default")
      (node (ref "R49") (pin "2") (pinfunction "2_2") (pintype "passive"))
      (node (ref "VIEW_SOC") (pin "P$1") (pinfunction "P$1_P$1") (pintype "bidirectional"))
      (node (ref "VIEW_SOC") (pin "P$2") (pinfunction "P$1_P$2") (pintype "bidirectional"))
    )
    (net (code "81") (name "Net-(SEL_SWITCH-Pad11)") (class "Default")
      (node (ref "SEL_SWITCH") (pin "11") (pinfunction "11_11") (pintype "bidirectional"))
      (node (ref "SEL_SWITCH") (pin "7") (pinfunction "7_7") (pintype "bidirectional"))
    )
    (net (code "82") (name "Net-(U$1-SDA)") (class "Default")
      (node (ref "I2C_SELECT") (pin "1") (pinfunction "1_1") (pintype "passive"))
      (node (ref "R29") (pin "2") (pinfunction "2_2") (pintype "passive"))
      (node (ref "U$1") (pin "A4") (pinfunction "SDA_A4") (pintype "bidirectional"))
    )
    (net (code "83") (name "unconnected-(GAUGE-P5{slash}HDQ-Pad12)") (class "Default")
      (node (ref "GAUGE") (pin "12") (pinfunction "P5/HDQ_12") (pintype "bidirectional"))
    )
    (net (code "84") (name "unconnected-(GAUGE-P6{slash}TS-Pad11)") (class "Default")
      (node (ref "GAUGE") (pin "11") (pinfunction "P6/TS_11") (pintype "bidirectional"))
    )
    (net (code "85") (name "unconnected-(PROTECTION-TS-Pad13)") (class "Default")
      (node (ref "PROTECTION") (pin "13") (pinfunction "TS_13") (pintype "bidirectional"))
    )
    (net (code "86") (name "unconnected-(PROTECTION-VTSB-Pad15)") (class "Default")
      (node (ref "PROTECTION") (pin "15") (pinfunction "VTSB_15") (pintype "bidirectional"))
    )
    (net (code "87") (name "unconnected-(SEL_SWITCH-Pad1)") (class "Default")
      (node (ref "SEL_SWITCH") (pin "1") (pinfunction "1_1") (pintype "bidirectional"))
    )
    (net (code "88") (name "unconnected-(SEL_SWITCH-Pad2)") (class "Default")
      (node (ref "SEL_SWITCH") (pin "2") (pinfunction "2_2") (pintype "bidirectional"))
    )
    (net (code "89") (name "unconnected-(SEL_SWITCH-Pad5)") (class "Default")
      (node (ref "SEL_SWITCH") (pin "5") (pinfunction "5_5") (pintype "bidirectional"))
    )
    (net (code "90") (name "unconnected-(SEL_SWITCH-Pad6)") (class "Default")
      (node (ref "SEL_SWITCH") (pin "6") (pinfunction "6_6") (pintype "bidirectional"))
    )
    (net (code "91") (name "unconnected-(SEL_SWITCH-Pad9)") (class "Default")
      (node (ref "SEL_SWITCH") (pin "9") (pinfunction "9_9") (pintype "bidirectional"))
    )
    (net (code "92") (name "unconnected-(SEL_SWITCH-Pad12)") (class "Default")
      (node (ref "SEL_SWITCH") (pin "12") (pinfunction "12_12") (pintype "bidirectional"))
    )
    (net (code "93") (name "unconnected-(U$1-Pad2)") (class "Default")
      (node (ref "U$1") (pin "2") (pinfunction "2_2") (pintype "bidirectional"))
    )
    (net (code "94") (name "unconnected-(U$1-Pad3)") (class "Default")
      (node (ref "U$1") (pin "3") (pinfunction "3_3") (pintype "bidirectional"))
    )
    (net (code "95") (name "unconnected-(U$1-Pad4)") (class "Default")
      (node (ref "U$1") (pin "4") (pinfunction "4_4") (pintype "bidirectional"))
    )
    (net (code "96") (name "unconnected-(U$1-Pad5)") (class "Default")
      (node (ref "U$1") (pin "5") (pinfunction "5_5") (pintype "bidirectional"))
    )
    (net (code "97") (name "unconnected-(U$1-Pad6)") (class "Default")
      (node (ref "U$1") (pin "6") (pinfunction "6_6") (pintype "bidirectional"))
    )
    (net (code "98") (name "unconnected-(U$1-Pad7)") (class "Default")
      (node (ref "U$1") (pin "7") (pinfunction "7_7") (pintype "bidirectional"))
    )
    (net (code "99") (name "unconnected-(U$1-Pad12)") (class "Default")
      (node (ref "U$1") (pin "12") (pinfunction "12_12") (pintype "bidirectional"))
    )
    (net (code "100") (name "unconnected-(U$1-Pad13)") (class "Default")
      (node (ref "U$1") (pin "13") (pinfunction "13_13") (pintype "bidirectional"))
    )
    (net (code "101") (name "unconnected-(U$1-PadA0)") (class "Default")
      (node (ref "U$1") (pin "A0") (pinfunction "A0_A0") (pintype "bidirectional"))
    )
    (net (code "102") (name "unconnected-(U$1-PadA1)") (class "Default")
      (node (ref "U$1") (pin "A1") (pinfunction "A1_A1") (pintype "bidirectional"))
    )
    (net (code "103") (name "unconnected-(U$1-PadA2)") (class "Default")
      (node (ref "U$1") (pin "A2") (pinfunction "A2_A2") (pintype "bidirectional"))
    )
    (net (code "104") (name "unconnected-(U$1-PadA3)") (class "Default")
      (node (ref "U$1") (pin "A3") (pinfunction "A3_A3") (pintype "bidirectional"))
    )
    (net (code "105") (name "unconnected-(U$1-PadA6)") (class "Default")
      (node (ref "U$1") (pin "A6") (pinfunction "A6_A6") (pintype "bidirectional"))
    )
    (net (code "106") (name "unconnected-(U$1-PadA7)") (class "Default")
      (node (ref "U$1") (pin "A7") (pinfunction "A7_A7") (pintype "bidirectional"))
    )
    (net (code "107") (name "unconnected-(U$1-PadBLK)") (class "Default")
      (node (ref "U$1") (pin "BLK") (pinfunction "BLK_BLK") (pintype "bidirectional"))
    )
    (net (code "108") (name "unconnected-(U$1-PadGRN)") (class "Default")
      (node (ref "U$1") (pin "GRN") (pinfunction "GRN_GRN") (pintype "bidirectional"))
    )
    (net (code "109") (name "unconnected-(U$1-PadRAW)") (class "Default")
      (node (ref "U$1") (pin "RAW") (pinfunction "RAW_RAW") (pintype "bidirectional"))
    )
    (net (code "110") (name "unconnected-(U$1-PadRST)") (class "Default")
      (node (ref "U$1") (pin "RST") (pinfunction "RST_RST") (pintype "bidirectional"))
    )
  )
)
